# untitled.net
KiCad netlist of a schematic drawn in EAGLE
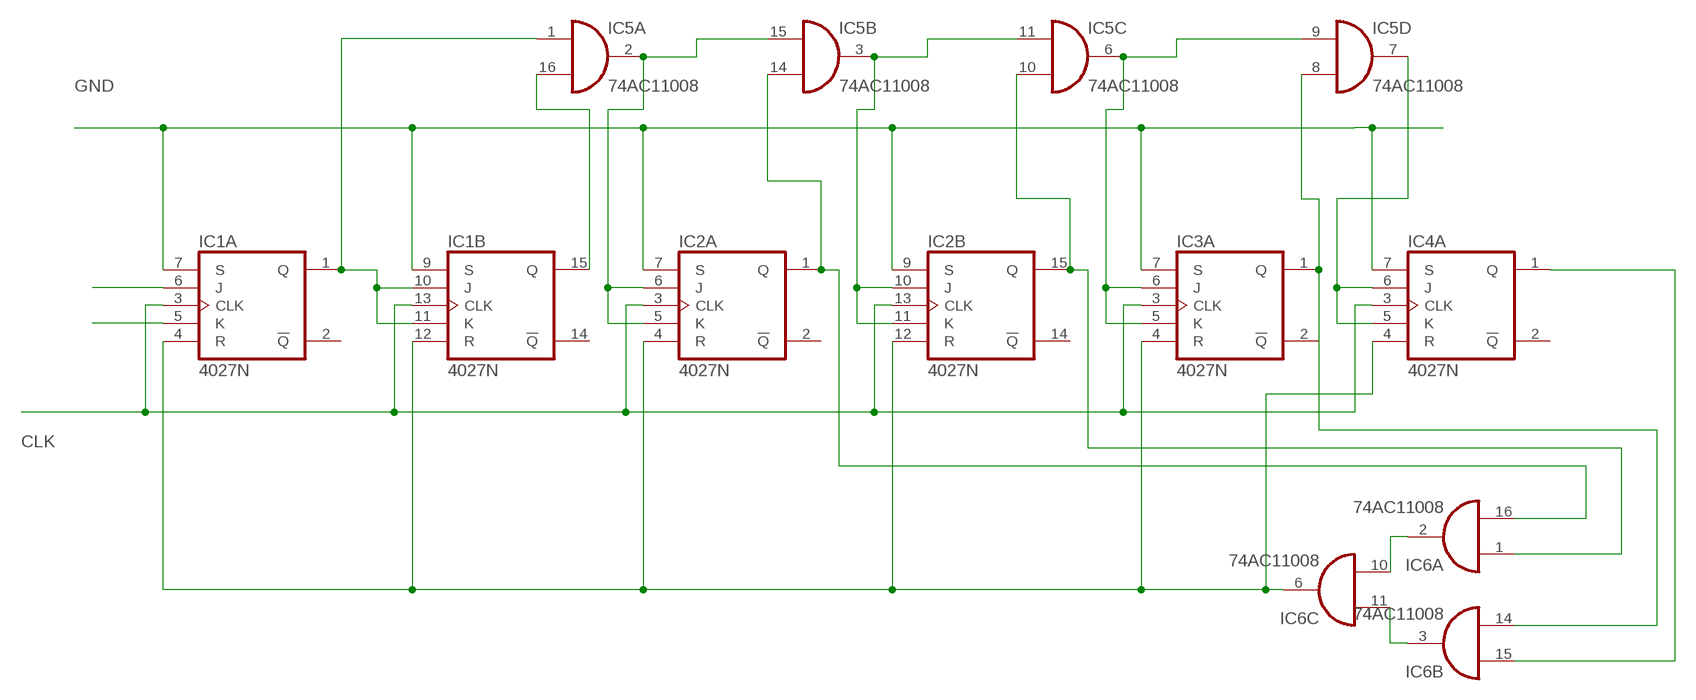
[diagram p0: schematic, sheet 1]

(export (version "E")
  (design (tool "Eeschema 10.0.6"))
  (components
    (comp (ref "IC1")
      (value "4027N")
      (footprint "eagle-import:DIL16")
      (libsource (lib "eagle-import") (part "4027N"))
    )
    (comp (ref "IC2")
      (value "4027N")
      (footprint "eagle-import:DIL16")
      (libsource (lib "eagle-import") (part "4027N"))
    )
    (comp (ref "IC3")
      (value "4027N")
      (footprint "eagle-import:DIL16")
      (libsource (lib "eagle-import") (part "4027N"))
    )
    (comp (ref "IC4")
      (value "4027N")
      (footprint "eagle-import:DIL16")
      (libsource (lib "eagle-import") (part "4027N"))
    )
    (comp (ref "IC5")
      (value "74AC11008")
      (footprint "eagle-import:DIL16")
      (libsource (lib "eagle-import") (part "74AC11008"))
    )
    (comp (ref "IC6")
      (value "74AC11008")
      (footprint "eagle-import:DIL16")
      (libsource (lib "eagle-import") (part "74AC11008"))
    )
  )
  (nets
    (net (code "1") (name "/CLK") (class "Default")
      (node (ref "IC1") (pin "13") (pinfunction "CLK_13") (pintype "input"))
      (node (ref "IC1") (pin "3") (pinfunction "CLK_3") (pintype "input"))
      (node (ref "IC2") (pin "13") (pinfunction "CLK_13") (pintype "input"))
      (node (ref "IC2") (pin "3") (pinfunction "CLK_3") (pintype "input"))
      (node (ref "IC3") (pin "3") (pinfunction "CLK_3") (pintype "input"))
      (node (ref "IC4") (pin "3") (pinfunction "CLK_3") (pintype "input"))
    )
    (net (code "2") (name "/GND") (class "Default")
      (node (ref "IC1") (pin "7") (pinfunction "S_7") (pintype "input"))
      (node (ref "IC1") (pin "9") (pinfunction "S_9") (pintype "input"))
      (node (ref "IC2") (pin "7") (pinfunction "S_7") (pintype "input"))
      (node (ref "IC2") (pin "9") (pinfunction "S_9") (pintype "input"))
      (node (ref "IC3") (pin "7") (pinfunction "S_7") (pintype "input"))
      (node (ref "IC4") (pin "7") (pinfunction "S_7") (pintype "input"))
    )
    (net (code "3") (name "Net-(IC1A-Q)") (class "Default")
      (node (ref "IC1") (pin "1") (pinfunction "Q_1") (pintype "output"))
      (node (ref "IC1") (pin "10") (pinfunction "J_10") (pintype "input"))
      (node (ref "IC1") (pin "11") (pinfunction "K_11") (pintype "input"))
      (node (ref "IC5") (pin "1") (pinfunction "I0_1") (pintype "input"))
    )
    (net (code "4") (name "Net-(IC1A-R)") (class "Default")
      (node (ref "IC1") (pin "12") (pinfunction "R_12") (pintype "input"))
      (node (ref "IC1") (pin "4") (pinfunction "R_4") (pintype "input"))
      (node (ref "IC2") (pin "12") (pinfunction "R_12") (pintype "input"))
      (node (ref "IC2") (pin "4") (pinfunction "R_4") (pintype "input"))
      (node (ref "IC3") (pin "4") (pinfunction "R_4") (pintype "input"))
      (node (ref "IC4") (pin "4") (pinfunction "R_4") (pintype "input"))
      (node (ref "IC6") (pin "6") (pinfunction "O_6") (pintype "output"))
    )
    (net (code "5") (name "Net-(IC1B-Q)") (class "Default")
      (node (ref "IC1") (pin "15") (pinfunction "Q_15") (pintype "output"))
      (node (ref "IC5") (pin "16") (pinfunction "I1_16") (pintype "input"))
    )
    (net (code "6") (name "Net-(IC2A-J)") (class "Default")
      (node (ref "IC2") (pin "5") (pinfunction "K_5") (pintype "input"))
      (node (ref "IC2") (pin "6") (pinfunction "J_6") (pintype "input"))
      (node (ref "IC5") (pin "15") (pinfunction "I0_15") (pintype "input"))
      (node (ref "IC5") (pin "2") (pinfunction "O_2") (pintype "output"))
    )
    (net (code "7") (name "Net-(IC2A-Q)") (class "Default")
      (node (ref "IC2") (pin "1") (pinfunction "Q_1") (pintype "output"))
      (node (ref "IC5") (pin "14") (pinfunction "I1_14") (pintype "input"))
      (node (ref "IC6") (pin "16") (pinfunction "I1_16") (pintype "input"))
    )
    (net (code "8") (name "Net-(IC2B-J)") (class "Default")
      (node (ref "IC2") (pin "10") (pinfunction "J_10") (pintype "input"))
      (node (ref "IC2") (pin "11") (pinfunction "K_11") (pintype "input"))
      (node (ref "IC5") (pin "11") (pinfunction "I0_11") (pintype "input"))
      (node (ref "IC5") (pin "3") (pinfunction "O_3") (pintype "output"))
    )
    (net (code "9") (name "Net-(IC2B-Q)") (class "Default")
      (node (ref "IC2") (pin "15") (pinfunction "Q_15") (pintype "output"))
      (node (ref "IC5") (pin "10") (pinfunction "I1_10") (pintype "input"))
      (node (ref "IC6") (pin "1") (pinfunction "I0_1") (pintype "input"))
    )
    (net (code "10") (name "Net-(IC3A-J)") (class "Default")
      (node (ref "IC3") (pin "5") (pinfunction "K_5") (pintype "input"))
      (node (ref "IC3") (pin "6") (pinfunction "J_6") (pintype "input"))
      (node (ref "IC5") (pin "6") (pinfunction "O_6") (pintype "output"))
      (node (ref "IC5") (pin "9") (pinfunction "I0_9") (pintype "input"))
    )
    (net (code "11") (name "Net-(IC3A-Q)") (class "Default")
      (node (ref "IC3") (pin "1") (pinfunction "Q_1") (pintype "output"))
      (node (ref "IC3") (pin "2") (pinfunction "~{Q}_2") (pintype "output"))
      (node (ref "IC5") (pin "8") (pinfunction "I1_8") (pintype "input"))
      (node (ref "IC6") (pin "14") (pinfunction "I1_14") (pintype "input"))
    )
    (net (code "12") (name "Net-(IC4A-J)") (class "Default")
      (node (ref "IC4") (pin "5") (pinfunction "K_5") (pintype "input"))
      (node (ref "IC4") (pin "6") (pinfunction "J_6") (pintype "input"))
      (node (ref "IC5") (pin "7") (pinfunction "O_7") (pintype "output"))
    )
    (net (code "13") (name "Net-(IC4A-Q)") (class "Default")
      (node (ref "IC4") (pin "1") (pinfunction "Q_1") (pintype "output"))
      (node (ref "IC6") (pin "15") (pinfunction "I0_15") (pintype "input"))
    )
    (net (code "14") (name "Net-(IC6A-O)") (class "Default")
      (node (ref "IC6") (pin "10") (pinfunction "I1_10") (pintype "input"))
      (node (ref "IC6") (pin "2") (pinfunction "O_2") (pintype "output"))
    )
    (net (code "15") (name "Net-(IC6B-O)") (class "Default")
      (node (ref "IC6") (pin "11") (pinfunction "I0_11") (pintype "input"))
      (node (ref "IC6") (pin "3") (pinfunction "O_3") (pintype "output"))
    )
    (net (code "16") (name "unconnected-(IC1A-J-Pad6)") (class "Default")
      (node (ref "IC1") (pin "6") (pinfunction "J_6") (pintype "input"))
    )
    (net (code "17") (name "unconnected-(IC1A-K-Pad5)") (class "Default")
      (node (ref "IC1") (pin "5") (pinfunction "K_5") (pintype "input"))
    )
    (net (code "18") (name "unconnected-(IC1A-~{Q}-Pad2)") (class "Default")
      (node (ref "IC1") (pin "2") (pinfunction "~{Q}_2") (pintype "output"))
    )
    (net (code "19") (name "unconnected-(IC1B-~{Q}-Pad14)") (class "Default")
      (node (ref "IC1") (pin "14") (pinfunction "~{Q}_14") (pintype "output"))
    )
    (net (code "20") (name "unconnected-(IC2A-~{Q}-Pad2)") (class "Default")
      (node (ref "IC2") (pin "2") (pinfunction "~{Q}_2") (pintype "output"))
    )
    (net (code "21") (name "unconnected-(IC2B-~{Q}-Pad14)") (class "Default")
      (node (ref "IC2") (pin "14") (pinfunction "~{Q}_14") (pintype "output"))
    )
    (net (code "22") (name "unconnected-(IC4A-~{Q}-Pad2)") (class "Default")
      (node (ref "IC4") (pin "2") (pinfunction "~{Q}_2") (pintype "output"))
    )
  )
)
